# SchR1_Propu.net
KiCad netlist of a schematic drawn in Altium Designer
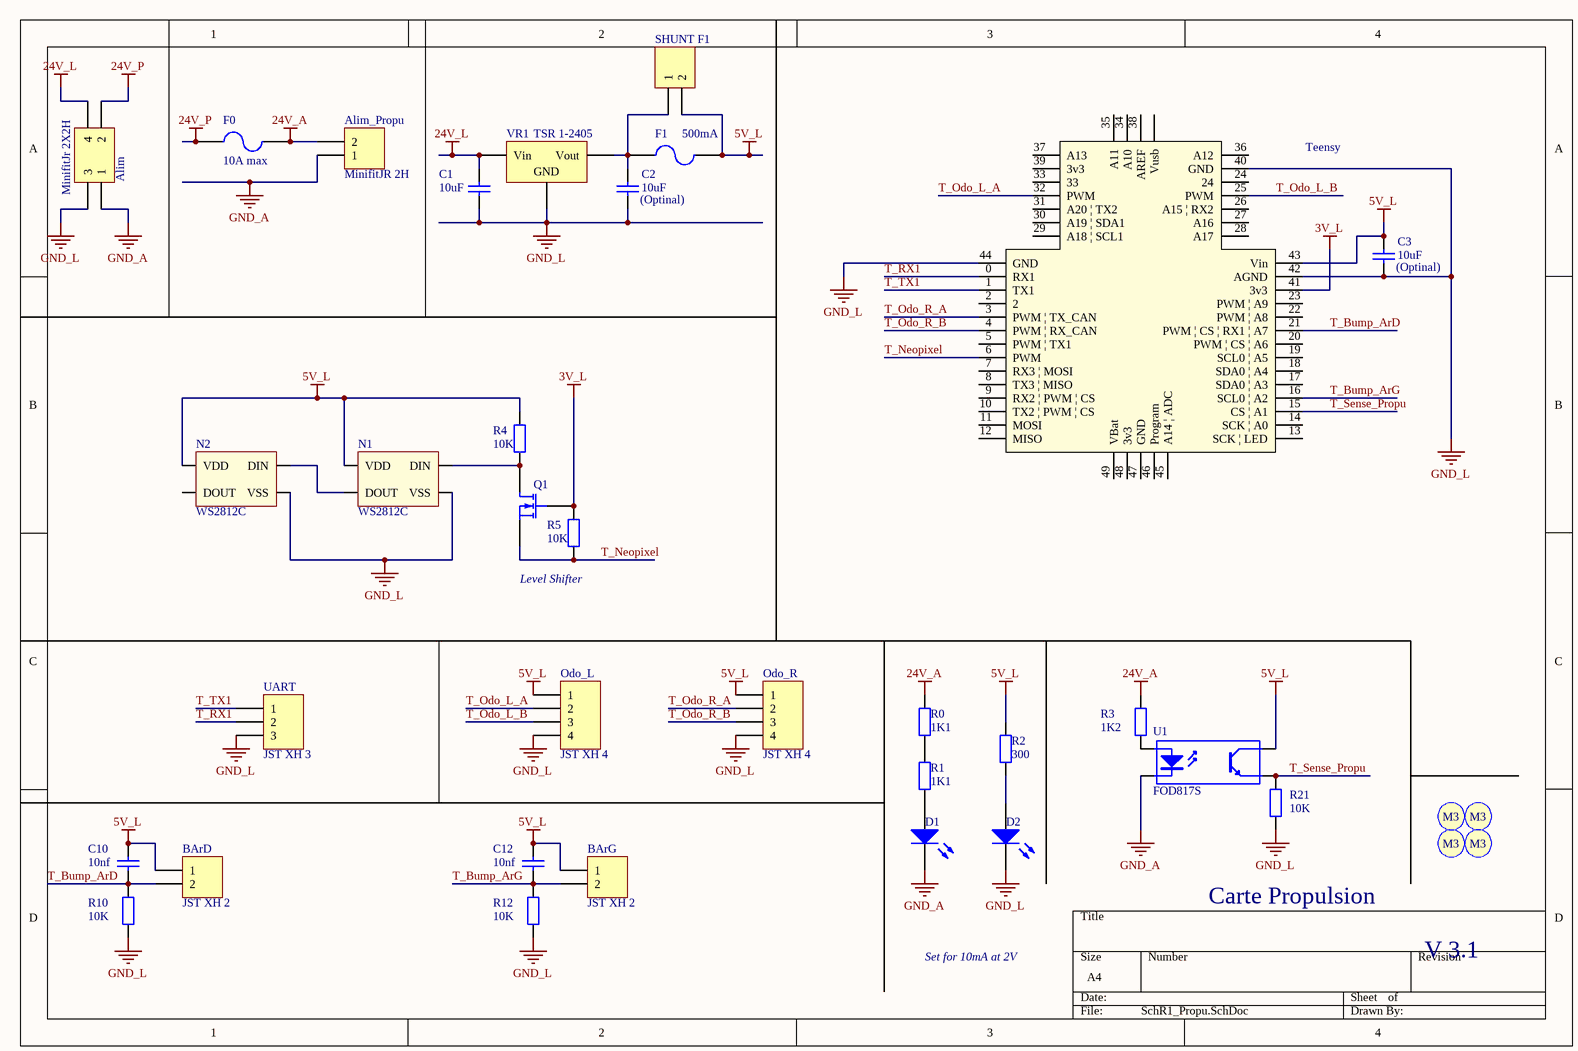
[diagram p0: SchR1_Propu.SchDoc]

(export (version "E")
  (design (tool "Eeschema 10.0.6"))
  (components
    (comp (ref "Alim")
      (value "MinifitJr 2X2H")
      (footprint "MOLEX_MINIFITJR_2X2H")
      (description "Header, 2-Pin, Dual row, Right Angle")
      (fields (field (name "PUBLISHER") "Altium Limited"))
      (libsource (lib "Miscellaneous Connectors") (part "Header 2X2H"))
    )
    (comp (ref "Alim_Propu")
      (value "MinifitJR 2H")
      (footprint "Molex_MiniFitJr_2x1H")
      (description "Header, 2-Pin")
      (fields (field (name "PUBLISHER") "Altium Limited"))
      (libsource (lib "Miscellaneous Connectors") (part "Header 2"))
    )
    (comp (ref "BArD")
      (value "JST XH 2")
      (footprint "S2B-XH-A")
      (description "Header, 2-Pin")
      (fields (field (name "PUBLISHER") "Altium Limited"))
      (libsource (lib "") (part "Header 2_1"))
    )
    (comp (ref "BArG")
      (value "JST XH 2")
      (footprint "S2B-XH-A")
      (description "Header, 2-Pin")
      (fields (field (name "PUBLISHER") "Altium Limited"))
      (libsource (lib "") (part "Header 2_1"))
    )
    (comp (ref "C1")
      (value "10uF")
      (footprint "Capacitor 1206")
      (description "Capacitor")
      (fields (field (name "PUBLISHER") "Altium Limited"))
      (libsource (lib "Miscellaneous Devices") (part "Cap"))
    )
    (comp (ref "C2")
      (value "(Optinal)")
      (footprint "Capacitor 1206")
      (description "Capacitor")
      (fields (field (name "ALTIUM_VALUE") "10uF") (field (name "PUBLISHER") "Altium Limited"))
      (libsource (lib "Miscellaneous Devices") (part "Cap"))
    )
    (comp (ref "C3")
      (value "(Optinal)")
      (footprint "Capacitor 1206")
      (description "Capacitor")
      (fields (field (name "ALTIUM_VALUE") "10uF") (field (name "PUBLISHER") "Altium Limited"))
      (libsource (lib "Miscellaneous Devices") (part "Cap"))
    )
    (comp (ref "C10")
      (value "10nf")
      (footprint "Capacitor 1206")
      (description "Capacitor")
      (fields (field (name "Comment") "Cap") (field (name "PUBLISHER") "Altium Limited"))
      (libsource (lib "Miscellaneous Devices") (part "Cap"))
    )
    (comp (ref "C12")
      (value "10nf")
      (footprint "Capacitor 1206")
      (description "Capacitor")
      (fields (field (name "Comment") "Cap") (field (name "PUBLISHER") "Altium Limited"))
      (libsource (lib "Miscellaneous Devices") (part "Cap"))
    )
    (comp (ref "D1")
      (value "A")
      (footprint "KP-3216SEC")
      (description "Typical RED, GREEN, YELLOW, AMBER GaAs LED")
      (fields (field (name "PUBLISHER") "Altium Limited"))
      (libsource (lib "Miscellaneous Devices") (part "LED2"))
    )
    (comp (ref "D2")
      (value "L")
      (footprint "KP-3216SEC")
      (description "Typical RED, GREEN, YELLOW, AMBER GaAs LED")
      (fields (field (name "PUBLISHER") "Altium Limited"))
      (libsource (lib "Miscellaneous Devices") (part "LED2"))
    )
    (comp (ref "F0")
      (value "10A max")
      (footprint "Fuse")
      (description "Main Fuse")
      (fields (field (name "PUBLISHER") "Altium Limited"))
      (libsource (lib "Miscellaneous Devices") (part "Fuse 2"))
    )
    (comp (ref "F1")
      (value "500mA")
      (footprint "3.5X2.8X1.9")
      (description "Fuse")
      (fields (field (name "PUBLISHER") "Altium Limited"))
      (libsource (lib "Miscellaneous Devices") (part "Fuse 2"))
    )
    (comp (ref "N1")
      (value "WS2812C")
      (footprint "Robot_2020:Neopixel")
      (description "Intelligent control LED")
      (libsource (lib "Robot_2020") (part "WS2812C"))
    )
    (comp (ref "N2")
      (value "WS2812C")
      (footprint "Robot_2020:Neopixel")
      (description "Intelligent control LED")
      (libsource (lib "Robot_2020") (part "WS2812C"))
    )
    (comp (ref "Odo_L")
      (value "JST XH 4")
      (footprint "S4B-XH-A")
      (description "Molex SPOX 4x1H")
      (fields (field (name "PUBLISHER") "Altium Limited"))
      (libsource (lib "Miscellaneous Connectors") (part "Header 4H"))
    )
    (comp (ref "Odo_R")
      (value "JST XH 4")
      (footprint "S4B-XH-A")
      (description "Molex SPOX 4x1H")
      (fields (field (name "PUBLISHER") "Altium Limited"))
      (libsource (lib "Miscellaneous Connectors") (part "Header 4H"))
    )
    (comp (ref "Q1")
      (value "MOSFET-N")
      (footprint "SOT23_M")
      (description "N-Channel MOSFET")
      (fields (field (name "PUBLISHER") "Altium Limited"))
      (libsource (lib "Miscellaneous Devices") (part "MOSFET-N"))
    )
    (comp (ref "R0")
      (value "1K1")
      (footprint "Resistor 1206")
      (description "Resistor")
      (fields (field (name "Comment") "Res2") (field (name "PUBLISHER") "Altium Limited"))
      (libsource (lib "Miscellaneous Devices") (part "Res2"))
    )
    (comp (ref "R1")
      (value "1K1")
      (footprint "Resistor 1206")
      (description "Resistor")
      (fields (field (name "Comment") "Res2") (field (name "PUBLISHER") "Altium Limited"))
      (libsource (lib "Miscellaneous Devices") (part "Res2"))
    )
    (comp (ref "R2")
      (value "300")
      (footprint "Resistor 1206")
      (description "Resistor")
      (fields (field (name "Comment") "Res2") (field (name "PUBLISHER") "Altium Limited"))
      (libsource (lib "Miscellaneous Devices") (part "Res2"))
    )
    (comp (ref "R3")
      (value "1K2")
      (footprint "Resistor 1206")
      (description "Resistor")
      (fields (field (name "Comment") "Res2") (field (name "PUBLISHER") "Altium Limited"))
      (libsource (lib "") (part "Res2_1"))
    )
    (comp (ref "R4")
      (value "10K")
      (footprint "Resistor 1206")
      (description "Resistor")
      (fields (field (name "Comment") "Res2") (field (name "PUBLISHER") "Altium Limited"))
      (libsource (lib "") (part "Res2_1"))
    )
    (comp (ref "R5")
      (value "10K")
      (footprint "Resistor 1206")
      (description "Resistor")
      (fields (field (name "Comment") "Res2") (field (name "PUBLISHER") "Altium Limited"))
      (libsource (lib "") (part "Res2_1"))
    )
    (comp (ref "R10")
      (value "10K")
      (footprint "Resistor 1206")
      (description "Resistor")
      (fields (field (name "Comment") "Res2") (field (name "PUBLISHER") "Altium Limited"))
      (libsource (lib "Miscellaneous Devices") (part "Res2"))
    )
    (comp (ref "R12")
      (value "10K")
      (footprint "Resistor 1206")
      (description "Resistor")
      (fields (field (name "Comment") "Res2") (field (name "PUBLISHER") "Altium Limited"))
      (libsource (lib "Miscellaneous Devices") (part "Res2"))
    )
    (comp (ref "R21")
      (value "10K")
      (footprint "Resistor 1206")
      (description "Resistor")
      (fields (field (name "Comment") "Res2") (field (name "PUBLISHER") "Altium Limited"))
      (libsource (lib "") (part "Res2_1"))
    )
    (comp (ref "S1")
      (value "Screw M3")
      (footprint "Screw M3")
      (libsource (lib "Robot_2019") (part "Screw M3"))
    )
    (comp (ref "S2")
      (value "Screw M3")
      (footprint "Screw M3")
      (libsource (lib "Robot_2019") (part "Screw M3"))
    )
    (comp (ref "S3")
      (value "Screw M3")
      (footprint "Screw M3")
      (libsource (lib "Robot_2019") (part "Screw M3"))
    )
    (comp (ref "S4")
      (value "Screw M3")
      (footprint "Screw M3")
      (libsource (lib "Robot_2019") (part "Screw M3"))
    )
    (comp (ref "SHUNT F1")
      (value "Header 2")
      (footprint "HDR1X2")
      (description "Header, 2-Pin")
      (fields (field (name "PUBLISHER") "Altium Limited"))
      (libsource (lib "Miscellaneous Connectors") (part "Header 2"))
    )
    (comp (ref "Teensy")
      (value "Teensy 3.2")
      (footprint "teensy")
      (libsource (lib "Robot_2020") (part "teensy3.2"))
    )
    (comp (ref "U1")
      (value "FOD817S")
      (footprint "SOP254P1016X385-4N")
      (description "4-Pin Phototransistor Optocoupler")
      (fields (field (name "PUBLISHER") "Altium Limited"))
      (libsource (lib "Miscellaneous Devices") (part "Optoisolator1"))
    )
    (comp (ref "UART")
      (value "JST XH 3")
      (footprint "HDR1X3H")
      (description "Header, 3-Pin, Right Angle")
      (fields (field (name "PUBLISHER") "Altium Limited"))
      (libsource (lib "Miscellaneous Connectors") (part "Header 3H"))
    )
    (comp (ref "VR1")
      (value "TSR 1-2405")
      (footprint "TRS")
      (description "Voltage Regulator")
      (fields (field (name "PUBLISHER") "Altium Limited"))
      (libsource (lib "Miscellaneous Devices") (part "Volt Reg"))
    )
  )
  (nets
    (net (code "1") (name "/T_Bump_ArD") (class "Default")
      (node (ref "BArD") (pin "2") (pinfunction "2_2") (pintype "passive"))
      (node (ref "C10") (pin "1") (pinfunction "1_1") (pintype "passive"))
      (node (ref "R10") (pin "1") (pinfunction "1_1") (pintype "passive"))
      (node (ref "Teensy") (pin "21") (pinfunction "PWM_¦_CS_¦_RX1_¦_A7_21") (pintype "passive"))
    )
    (net (code "2") (name "/T_Bump_ArG") (class "Default")
      (node (ref "BArG") (pin "2") (pinfunction "2_2") (pintype "passive"))
      (node (ref "C12") (pin "1") (pinfunction "1_1") (pintype "passive"))
      (node (ref "R12") (pin "1") (pinfunction "1_1") (pintype "passive"))
      (node (ref "Teensy") (pin "16") (pinfunction "SCL0_¦_A2_16") (pintype "passive"))
    )
    (net (code "3") (name "/T_Neopixel") (class "Default")
      (node (ref "Q1") (pin "3") (pinfunction "S_3") (pintype "passive"))
      (node (ref "R5") (pin "1") (pinfunction "1_1") (pintype "passive"))
      (node (ref "Teensy") (pin "6") (pinfunction "PWM_6") (pintype "passive"))
    )
    (net (code "4") (name "/T_Odo_L_A") (class "Default")
      (node (ref "Odo_L") (pin "2") (pinfunction "2_2") (pintype "passive"))
      (node (ref "Teensy") (pin "32") (pinfunction "PWM_32") (pintype "passive"))
    )
    (net (code "5") (name "/T_Odo_L_B") (class "Default")
      (node (ref "Odo_L") (pin "3") (pinfunction "3_3") (pintype "passive"))
      (node (ref "Teensy") (pin "25") (pinfunction "PWM_25") (pintype "passive"))
    )
    (net (code "6") (name "/T_Odo_R_A") (class "Default")
      (node (ref "Odo_R") (pin "2") (pinfunction "2_2") (pintype "passive"))
      (node (ref "Teensy") (pin "3") (pinfunction "PWM_¦_TX_CAN_3") (pintype "passive"))
    )
    (net (code "7") (name "/T_Odo_R_B") (class "Default")
      (node (ref "Odo_R") (pin "3") (pinfunction "3_3") (pintype "passive"))
      (node (ref "Teensy") (pin "4") (pinfunction "PWM_¦_RX_CAN_4") (pintype "passive"))
    )
    (net (code "8") (name "/T_RX1") (class "Default")
      (node (ref "Teensy") (pin "0") (pinfunction "RX1_0") (pintype "passive"))
      (node (ref "UART") (pin "2") (pinfunction "2_2") (pintype "passive"))
    )
    (net (code "9") (name "/T_Sense_Propu") (class "Default")
      (node (ref "R21") (pin "2") (pinfunction "2_2") (pintype "passive"))
      (node (ref "Teensy") (pin "15") (pinfunction "CS_¦_A1_15") (pintype "passive"))
      (node (ref "U1") (pin "3") (pinfunction "E_3") (pintype "passive"))
    )
    (net (code "10") (name "/T_TX1") (class "Default")
      (node (ref "Teensy") (pin "1") (pinfunction "TX1_1") (pintype "passive"))
      (node (ref "UART") (pin "1") (pinfunction "1_1") (pintype "passive"))
    )
    (net (code "11") (name "3V_L") (class "Default")
      (node (ref "Q1") (pin "2") (pinfunction "G_2") (pintype "passive"))
      (node (ref "R5") (pin "2") (pinfunction "2_2") (pintype "passive"))
      (node (ref "Teensy") (pin "41") (pinfunction "3v3_41") (pintype "passive"))
    )
    (net (code "12") (name "5V_L") (class "Default")
      (node (ref "BArD") (pin "1") (pinfunction "1_1") (pintype "passive"))
      (node (ref "BArG") (pin "1") (pinfunction "1_1") (pintype "passive"))
      (node (ref "C10") (pin "2") (pinfunction "2_2") (pintype "passive"))
      (node (ref "C12") (pin "2") (pinfunction "2_2") (pintype "passive"))
      (node (ref "C3") (pin "2") (pinfunction "2_2") (pintype "passive"))
      (node (ref "F1") (pin "2") (pinfunction "2_2") (pintype "passive"))
      (node (ref "N1") (pin "1") (pinfunction "VDD_1") (pintype "passive"))
      (node (ref "N2") (pin "1") (pinfunction "VDD_1") (pintype "passive"))
      (node (ref "Odo_L") (pin "1") (pinfunction "1_1") (pintype "passive"))
      (node (ref "Odo_R") (pin "1") (pinfunction "1_1") (pintype "passive"))
      (node (ref "R2") (pin "1") (pinfunction "1_1") (pintype "passive"))
      (node (ref "R4") (pin "2") (pinfunction "2_2") (pintype "passive"))
      (node (ref "SHUNT F1") (pin "2") (pinfunction "2_2") (pintype "passive"))
      (node (ref "Teensy") (pin "43") (pinfunction "Vin_43") (pintype "passive"))
      (node (ref "U1") (pin "4") (pinfunction "C_4") (pintype "passive"))
    )
    (net (code "13") (name "24V_A") (class "Default")
      (node (ref "Alim_Propu") (pin "2") (pinfunction "2_2") (pintype "passive"))
      (node (ref "F0") (pin "2") (pinfunction "2_2") (pintype "passive"))
      (node (ref "R0") (pin "1") (pinfunction "1_1") (pintype "passive"))
      (node (ref "R3") (pin "2") (pinfunction "2_2") (pintype "passive"))
    )
    (net (code "14") (name "24V_L") (class "Default")
      (node (ref "Alim") (pin "4") (pinfunction "4_4") (pintype "passive"))
      (node (ref "C1") (pin "2") (pinfunction "2_2") (pintype "passive"))
      (node (ref "VR1") (pin "1") (pinfunction "Vin_1") (pintype "passive"))
    )
    (net (code "15") (name "24V_P") (class "Default")
      (node (ref "Alim") (pin "2") (pinfunction "2_2") (pintype "passive"))
      (node (ref "F0") (pin "1") (pinfunction "1_1") (pintype "passive"))
    )
    (net (code "16") (name "GND_A") (class "Default")
      (node (ref "Alim") (pin "1") (pinfunction "1_1") (pintype "passive"))
      (node (ref "Alim_Propu") (pin "1") (pinfunction "1_1") (pintype "passive"))
      (node (ref "D1") (pin "2") (pinfunction "K_2") (pintype "passive"))
      (node (ref "U1") (pin "2") (pinfunction "K_2") (pintype "passive"))
    )
    (net (code "17") (name "GND_L") (class "Default")
      (node (ref "Alim") (pin "3") (pinfunction "3_3") (pintype "passive"))
      (node (ref "C1") (pin "1") (pinfunction "1_1") (pintype "passive"))
      (node (ref "C2") (pin "1") (pinfunction "1_1") (pintype "passive"))
      (node (ref "C3") (pin "1") (pinfunction "1_1") (pintype "passive"))
      (node (ref "D2") (pin "2") (pinfunction "K_2") (pintype "passive"))
      (node (ref "N1") (pin "3") (pinfunction "VSS_3") (pintype "passive"))
      (node (ref "N2") (pin "3") (pinfunction "VSS_3") (pintype "passive"))
      (node (ref "Odo_L") (pin "4") (pinfunction "4_4") (pintype "passive"))
      (node (ref "Odo_R") (pin "4") (pinfunction "4_4") (pintype "passive"))
      (node (ref "R10") (pin "2") (pinfunction "2_2") (pintype "passive"))
      (node (ref "R12") (pin "2") (pinfunction "2_2") (pintype "passive"))
      (node (ref "R21") (pin "1") (pinfunction "1_1") (pintype "passive"))
      (node (ref "Teensy") (pin "40") (pinfunction "GND_40") (pintype "passive"))
      (node (ref "Teensy") (pin "42") (pinfunction "AGND_42") (pintype "passive"))
      (node (ref "Teensy") (pin "44") (pinfunction "GND_44") (pintype "passive"))
      (node (ref "UART") (pin "3") (pinfunction "3_3") (pintype "passive"))
      (node (ref "VR1") (pin "2") (pinfunction "GND_2") (pintype "passive"))
    )
    (net (code "18") (name "Net-(D1-A)") (class "Default")
      (node (ref "D1") (pin "1") (pinfunction "A_1") (pintype "passive"))
      (node (ref "R1") (pin "2") (pinfunction "2_2") (pintype "passive"))
    )
    (net (code "19") (name "Net-(D2-A)") (class "Default")
      (node (ref "D2") (pin "1") (pinfunction "A_1") (pintype "passive"))
      (node (ref "R2") (pin "2") (pinfunction "2_2") (pintype "passive"))
    )
    (net (code "20") (name "Net-(N1-DIN)") (class "Default")
      (node (ref "N1") (pin "4") (pinfunction "DIN_4") (pintype "passive"))
      (node (ref "Q1") (pin "1") (pinfunction "D_1") (pintype "passive"))
      (node (ref "R4") (pin "1") (pinfunction "1_1") (pintype "passive"))
    )
    (net (code "21") (name "Net-(N1-DOUT)") (class "Default")
      (node (ref "N1") (pin "2") (pinfunction "DOUT_2") (pintype "passive"))
      (node (ref "N2") (pin "4") (pinfunction "DIN_4") (pintype "passive"))
    )
    (net (code "22") (name "Net-(R0-Pad2)") (class "Default")
      (node (ref "R0") (pin "2") (pinfunction "2_2") (pintype "passive"))
      (node (ref "R1") (pin "1") (pinfunction "1_1") (pintype "passive"))
    )
    (net (code "23") (name "Net-(U1-A)") (class "Default")
      (node (ref "R3") (pin "1") (pinfunction "1_1") (pintype "passive"))
      (node (ref "U1") (pin "1") (pinfunction "A_1") (pintype "passive"))
    )
    (net (code "24") (name "Net-(VR1-Vout)") (class "Default")
      (node (ref "C2") (pin "2") (pinfunction "2_2") (pintype "passive"))
      (node (ref "F1") (pin "1") (pinfunction "1_1") (pintype "passive"))
      (node (ref "SHUNT F1") (pin "1") (pinfunction "1_1") (pintype "passive"))
      (node (ref "VR1") (pin "3") (pinfunction "Vout_3") (pintype "passive"))
    )
    (net (code "25") (name "unconnected-(N2-DOUT-Pad2)") (class "Default")
      (node (ref "N2") (pin "2") (pinfunction "DOUT_2") (pintype "passive"))
    )
    (net (code "26") (name "unconnected-(Teensy-3v3-Pad39)") (class "Default")
      (node (ref "Teensy") (pin "39") (pinfunction "3v3_39") (pintype "passive"))
    )
    (net (code "27") (name "unconnected-(Teensy-3v3-Pad48)") (class "Default")
      (node (ref "Teensy") (pin "48") (pinfunction "3v3_48") (pintype "passive"))
    )
    (net (code "28") (name "unconnected-(Teensy-A10-Pad34)") (class "Default")
      (node (ref "Teensy") (pin "34") (pinfunction "A10_34") (pintype "passive"))
    )
    (net (code "29") (name "unconnected-(Teensy-A11-Pad35)") (class "Default")
      (node (ref "Teensy") (pin "35") (pinfunction "A11_35") (pintype "passive"))
    )
    (net (code "30") (name "unconnected-(Teensy-A12-Pad36)") (class "Default")
      (node (ref "Teensy") (pin "36") (pinfunction "A12_36") (pintype "passive"))
    )
    (net (code "31") (name "unconnected-(Teensy-A13-Pad37)") (class "Default")
      (node (ref "Teensy") (pin "37") (pinfunction "A13_37") (pintype "passive"))
    )
    (net (code "32") (name "unconnected-(Teensy-A14_¦_ADC-Pad45)") (class "Default")
      (node (ref "Teensy") (pin "45") (pinfunction "A14_¦_ADC_45") (pintype "passive"))
    )
    (net (code "33") (name "unconnected-(Teensy-A15_¦_RX2-Pad26)") (class "Default")
      (node (ref "Teensy") (pin "26") (pinfunction "A15_¦_RX2_26") (pintype "passive"))
    )
    (net (code "34") (name "unconnected-(Teensy-A16-Pad27)") (class "Default")
      (node (ref "Teensy") (pin "27") (pinfunction "A16_27") (pintype "passive"))
    )
    (net (code "35") (name "unconnected-(Teensy-A17-Pad28)") (class "Default")
      (node (ref "Teensy") (pin "28") (pinfunction "A17_28") (pintype "passive"))
    )
    (net (code "36") (name "unconnected-(Teensy-A18_¦_SCL1-Pad29)") (class "Default")
      (node (ref "Teensy") (pin "29") (pinfunction "A18_¦_SCL1_29") (pintype "passive"))
    )
    (net (code "37") (name "unconnected-(Teensy-A19_¦_SDA1-Pad30)") (class "Default")
      (node (ref "Teensy") (pin "30") (pinfunction "A19_¦_SDA1_30") (pintype "passive"))
    )
    (net (code "38") (name "unconnected-(Teensy-A20_¦_TX2-Pad31)") (class "Default")
      (node (ref "Teensy") (pin "31") (pinfunction "A20_¦_TX2_31") (pintype "passive"))
    )
    (net (code "39") (name "unconnected-(Teensy-AREF-Pad38)") (class "Default")
      (node (ref "Teensy") (pin "38") (pinfunction "AREF_38") (pintype "passive"))
    )
    (net (code "40") (name "unconnected-(Teensy-GND-Pad47)") (class "Default")
      (node (ref "Teensy") (pin "47") (pinfunction "GND_47") (pintype "passive"))
    )
    (net (code "41") (name "unconnected-(Teensy-MISO-Pad12)") (class "Default")
      (node (ref "Teensy") (pin "12") (pinfunction "MISO_12") (pintype "passive"))
    )
    (net (code "42") (name "unconnected-(Teensy-MOSI-Pad11)") (class "Default")
      (node (ref "Teensy") (pin "11") (pinfunction "MOSI_11") (pintype "passive"))
    )
    (net (code "43") (name "unconnected-(Teensy-PWM_¦_A8-Pad22)") (class "Default")
      (node (ref "Teensy") (pin "22") (pinfunction "PWM_¦_A8_22") (pintype "passive"))
    )
    (net (code "44") (name "unconnected-(Teensy-PWM_¦_A9-Pad23)") (class "Default")
      (node (ref "Teensy") (pin "23") (pinfunction "PWM_¦_A9_23") (pintype "passive"))
    )
    (net (code "45") (name "unconnected-(Teensy-PWM_¦_CS_¦_A6-Pad20)") (class "Default")
      (node (ref "Teensy") (pin "20") (pinfunction "PWM_¦_CS_¦_A6_20") (pintype "passive"))
    )
    (net (code "46") (name "unconnected-(Teensy-PWM_¦_TX1-Pad5)") (class "Default")
      (node (ref "Teensy") (pin "5") (pinfunction "PWM_¦_TX1_5") (pintype "passive"))
    )
    (net (code "47") (name "unconnected-(Teensy-Pad2)") (class "Default")
      (node (ref "Teensy") (pin "2") (pinfunction "2_2") (pintype "passive"))
    )
    (net (code "48") (name "unconnected-(Teensy-Pad24)") (class "Default")
      (node (ref "Teensy") (pin "24") (pinfunction "24_24") (pintype "passive"))
    )
    (net (code "49") (name "unconnected-(Teensy-Pad33)") (class "Default")
      (node (ref "Teensy") (pin "33") (pinfunction "33_33") (pintype "passive"))
    )
    (net (code "50") (name "unconnected-(Teensy-Program-Pad46)") (class "Default")
      (node (ref "Teensy") (pin "46") (pinfunction "Program_46") (pintype "passive"))
    )
    (net (code "51") (name "unconnected-(Teensy-RX2_¦_PWM_¦_CS-Pad9)") (class "Default")
      (node (ref "Teensy") (pin "9") (pinfunction "RX2_¦_PWM_¦_CS_9") (pintype "passive"))
    )
    (net (code "52") (name "unconnected-(Teensy-RX3_¦_MOSI-Pad7)") (class "Default")
      (node (ref "Teensy") (pin "7") (pinfunction "RX3_¦_MOSI_7") (pintype "passive"))
    )
    (net (code "53") (name "unconnected-(Teensy-SCK_¦_A0-Pad14)") (class "Default")
      (node (ref "Teensy") (pin "14") (pinfunction "SCK_¦_A0_14") (pintype "passive"))
    )
    (net (code "54") (name "unconnected-(Teensy-SCK_¦_LED-Pad13)") (class "Default")
      (node (ref "Teensy") (pin "13") (pinfunction "SCK_¦_LED_13") (pintype "passive"))
    )
    (net (code "55") (name "unconnected-(Teensy-SCL0_¦_A5-Pad19)") (class "Default")
      (node (ref "Teensy") (pin "19") (pinfunction "SCL0_¦_A5_19") (pintype "passive"))
    )
    (net (code "56") (name "unconnected-(Teensy-SDA0_¦_A3-Pad17)") (class "Default")
      (node (ref "Teensy") (pin "17") (pinfunction "SDA0_¦_A3_17") (pintype "passive"))
    )
    (net (code "57") (name "unconnected-(Teensy-SDA0_¦_A4-Pad18)") (class "Default")
      (node (ref "Teensy") (pin "18") (pinfunction "SDA0_¦_A4_18") (pintype "passive"))
    )
    (net (code "58") (name "unconnected-(Teensy-TX2_¦_PWM_¦_CS-Pad10)") (class "Default")
      (node (ref "Teensy") (pin "10") (pinfunction "TX2_¦_PWM_¦_CS_10") (pintype "passive"))
    )
    (net (code "59") (name "unconnected-(Teensy-TX3_¦_MISO-Pad8)") (class "Default")
      (node (ref "Teensy") (pin "8") (pinfunction "TX3_¦_MISO_8") (pintype "passive"))
    )
    (net (code "60") (name "unconnected-(Teensy-VBat-Pad49)") (class "Default")
      (node (ref "Teensy") (pin "49") (pinfunction "VBat_49") (pintype "passive"))
    )
    (net (code "61") (name "unconnected-(Teensy-Vusb-Pad50)") (class "Default")
      (node (ref "Teensy") (pin "50") (pinfunction "Vusb_50") (pintype "passive"))
    )
  )
)
